# surficial_sensor.net
KiCad netlist of a schematic drawn in EAGLE
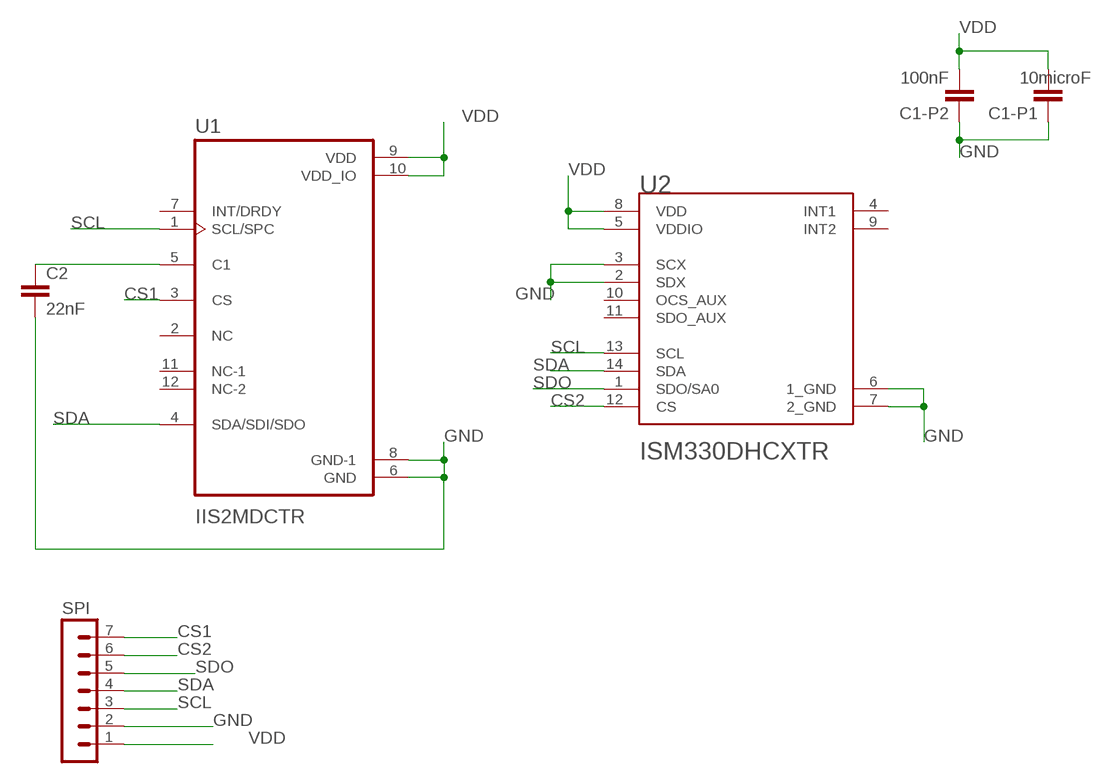
[diagram p0: schematic, sheet 1]

(export (version "E")
  (design (tool "Eeschema 10.0.6"))
  (components
    (comp (ref "C1-P1")
      (value "10microF")
      (footprint "eagle-import:C0603")
      (libsource (lib "eagle-import") (part "C-EUC0603"))
    )
    (comp (ref "C1-P2")
      (value "100nF")
      (footprint "eagle-import:C0603")
      (libsource (lib "eagle-import") (part "C-EUC0603"))
    )
    (comp (ref "C2")
      (value "22nF")
      (footprint "eagle-import:C0603")
      (libsource (lib "eagle-import") (part "C-EUC0603"))
    )
    (comp (ref "SPI")
      (value "MA07-1")
      (footprint "eagle-import:MA07-1")
      (libsource (lib "eagle-import") (part "MA07-1"))
    )
    (comp (ref "U1")
      (value "IIS2MDCTR")
      (footprint "eagle-import:LGA12R50P4X4_200X200X70")
      (fields (field (name "MF") "STMicroelectronics"))
      (libsource (lib "eagle-import") (part "IIS2MDCTR"))
    )
    (comp (ref "U2")
      (value "STMICROELECTRONICS_ISM330DHCXTRSTMICROELECTRONICS_ISM330DHCXTR_0_0")
      (footprint "eagle-import:STMICROELECTRONICS_ISM330DHCXTR_0")
      (fields
        (field (name "DIGIKEY_PART_NUMBER") "497-19784-1-ND")
        (field (name "MF") "STMicroelectronics")
        (field (name "MOUSER_PART_NUMBER") "511-ISM330DHCXTR")
      )
      (libsource (lib "eagle-import") (part "STMICROELECTRONICS_ISM330DHCXTRSTMICROELECTRONICS_ISM330DHCXTR_0_0"))
    )
  )
  (nets
    (net (code "1") (name "/CS1") (class "Default")
      (node (ref "SPI") (pin "7") (pinfunction "7_7") (pintype "passive"))
      (node (ref "U1") (pin "3") (pinfunction "CS_3") (pintype "bidirectional"))
    )
    (net (code "2") (name "/CS2") (class "Default")
      (node (ref "SPI") (pin "6") (pinfunction "6_6") (pintype "passive"))
      (node (ref "U2") (pin "12") (pinfunction "CS_12") (pintype "input"))
    )
    (net (code "3") (name "/GND") (class "Default")
      (node (ref "C1-P1") (pin "1") (pinfunction "1_1") (pintype "passive"))
      (node (ref "C1-P2") (pin "1") (pinfunction "1_1") (pintype "passive"))
      (node (ref "C2") (pin "2") (pinfunction "2_2") (pintype "passive"))
      (node (ref "SPI") (pin "2") (pinfunction "2_2") (pintype "passive"))
      (node (ref "U1") (pin "6") (pinfunction "GND_6") (pintype "power_in"))
      (node (ref "U1") (pin "8") (pinfunction "GND-1_8") (pintype "power_in"))
      (node (ref "U2") (pin "2") (pinfunction "SDX_2") (pintype "bidirectional"))
      (node (ref "U2") (pin "3") (pinfunction "SCX_3") (pintype "bidirectional"))
      (node (ref "U2") (pin "6") (pinfunction "1_GND_6") (pintype "power_in"))
      (node (ref "U2") (pin "7") (pinfunction "2_GND_7") (pintype "power_in"))
    )
    (net (code "4") (name "/SCL") (class "Default")
      (node (ref "SPI") (pin "3") (pinfunction "3_3") (pintype "passive"))
      (node (ref "U1") (pin "1") (pinfunction "SCL/SPC_1") (pintype "input"))
      (node (ref "U2") (pin "13") (pinfunction "SCL_13") (pintype "input"))
    )
    (net (code "5") (name "/SDA") (class "Default")
      (node (ref "SPI") (pin "4") (pinfunction "4_4") (pintype "passive"))
      (node (ref "U1") (pin "4") (pinfunction "SDA/SDI/SDO_4") (pintype "bidirectional"))
      (node (ref "U2") (pin "14") (pinfunction "SDA_14") (pintype "bidirectional"))
    )
    (net (code "6") (name "/SDO") (class "Default")
      (node (ref "SPI") (pin "5") (pinfunction "5_5") (pintype "passive"))
      (node (ref "U2") (pin "1") (pinfunction "SDO/SA0_1") (pintype "bidirectional"))
    )
    (net (code "7") (name "/VDD") (class "Default")
      (node (ref "C1-P1") (pin "2") (pinfunction "2_2") (pintype "passive"))
      (node (ref "C1-P2") (pin "2") (pinfunction "2_2") (pintype "passive"))
      (node (ref "SPI") (pin "1") (pinfunction "1_1") (pintype "passive"))
      (node (ref "U1") (pin "10") (pinfunction "VDD_IO_10") (pintype "power_in"))
      (node (ref "U1") (pin "9") (pinfunction "VDD_9") (pintype "power_in"))
      (node (ref "U2") (pin "5") (pinfunction "VDDIO_5") (pintype "power_in"))
      (node (ref "U2") (pin "8") (pinfunction "VDD_8") (pintype "power_in"))
    )
    (net (code "8") (name "Net-(U1-C1)") (class "Default")
      (node (ref "C2") (pin "1") (pinfunction "1_1") (pintype "passive"))
      (node (ref "U1") (pin "5") (pinfunction "C1_5") (pintype "bidirectional"))
    )
    (net (code "9") (name "unconnected-(U1-INT{slash}DRDY-Pad7)") (class "Default")
      (node (ref "U1") (pin "7") (pinfunction "INT/DRDY_7") (pintype "input"))
    )
    (net (code "10") (name "unconnected-(U1-NC-1-Pad11)") (class "Default")
      (node (ref "U1") (pin "11") (pinfunction "NC-1_11") (pintype "bidirectional"))
    )
    (net (code "11") (name "unconnected-(U1-NC-2-Pad12)") (class "Default")
      (node (ref "U1") (pin "12") (pinfunction "NC-2_12") (pintype "bidirectional"))
    )
    (net (code "12") (name "unconnected-(U1-NC-Pad2)") (class "Default")
      (node (ref "U1") (pin "2") (pinfunction "NC_2") (pintype "bidirectional"))
    )
    (net (code "13") (name "unconnected-(U2-INT1-Pad4)") (class "Default")
      (node (ref "U2") (pin "4") (pinfunction "INT1_4") (pintype "output"))
    )
    (net (code "14") (name "unconnected-(U2-INT2-Pad9)") (class "Default")
      (node (ref "U2") (pin "9") (pinfunction "INT2_9") (pintype "output"))
    )
    (net (code "15") (name "unconnected-(U2-OCS_AUX-Pad10)") (class "Default")
      (node (ref "U2") (pin "10") (pinfunction "OCS_AUX_10") (pintype "input"))
    )
    (net (code "16") (name "unconnected-(U2-SDO_AUX-Pad11)") (class "Default")
      (node (ref "U2") (pin "11") (pinfunction "SDO_AUX_11") (pintype "output"))
    )
  )
)
